# Solenoid_2.net
KiCad netlist of a schematic drawn in EAGLE
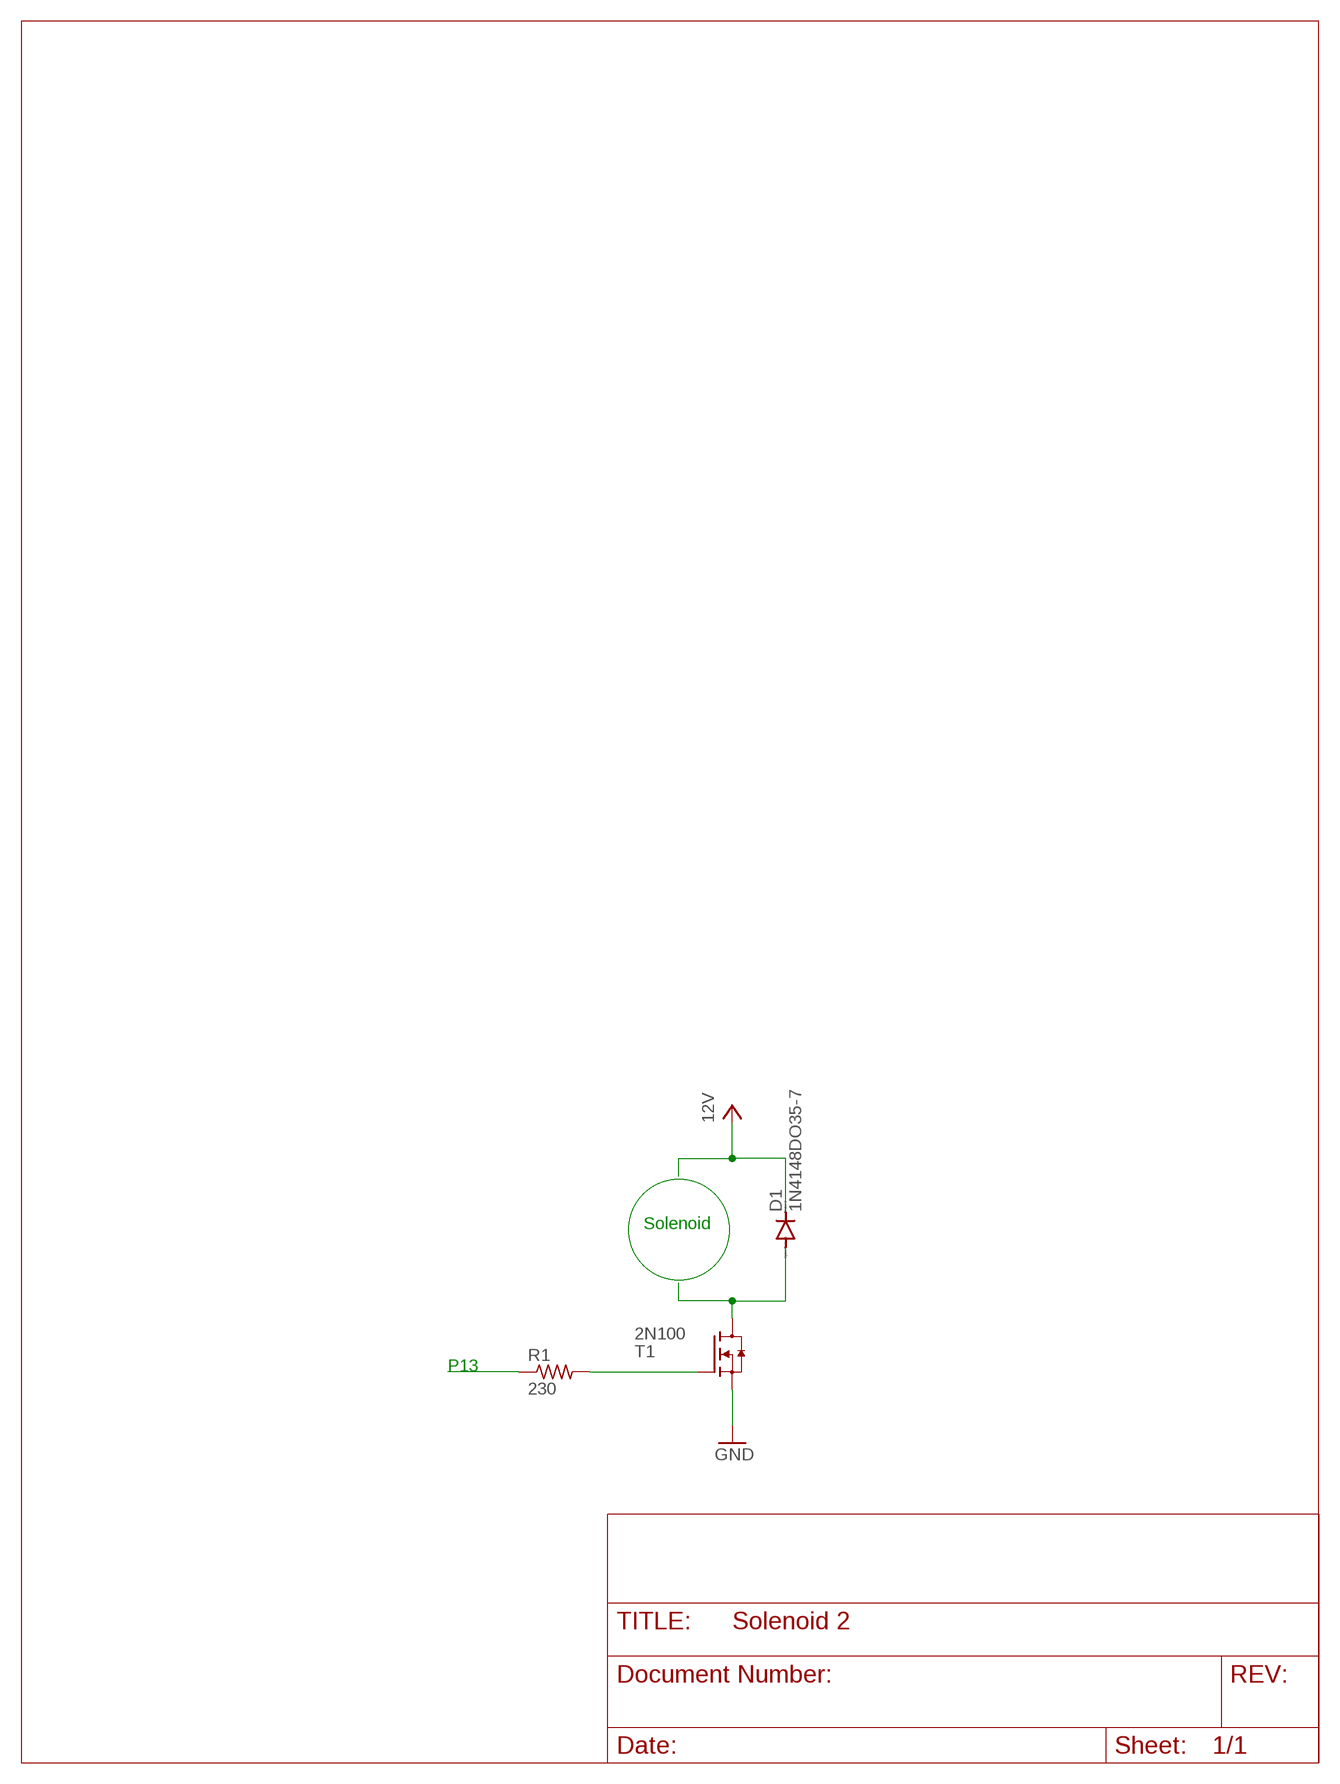
[diagram p0: schematic, sheet 1]

(export (version "E")
  (design (tool "Eeschema 10.0.6"))
  (components
    (comp (ref "D1")
      (value "1N4148DO35-7")
      (footprint "eagle-import:DO35-7")
      (libsource (lib "eagle-import") (part "1N4148DO35-7"))
    )
    (comp (ref "R1")
      (value "230")
      (footprint "eagle-import:0204_7")
      (libsource (lib "eagle-import") (part "R-US_0204/7"))
    )
    (comp (ref "T1")
      (value "2N100")
      (footprint "eagle-import:PG-TO263-7-3")
      (libsource (lib "eagle-import") (part "IPB180N06S4-H1"))
    )
  )
  (nets
    (net (code "1") (name "12V") (class "Default")
      (node (ref "D1") (pin "C") (pinfunction "C_C") (pintype "passive"))
    )
    (net (code "2") (name "GND") (class "Default")
      (node (ref "T1") (pin "2") (pinfunction "S_2") (pintype "passive"))
      (node (ref "T1") (pin "3") (pinfunction "S_3") (pintype "passive"))
      (node (ref "T1") (pin "5") (pinfunction "S_5") (pintype "passive"))
      (node (ref "T1") (pin "6") (pinfunction "S_6") (pintype "passive"))
      (node (ref "T1") (pin "7") (pinfunction "S_7") (pintype "passive"))
    )
    (net (code "3") (name "Net-(T1-D)") (class "Default")
      (node (ref "D1") (pin "A") (pinfunction "A_A") (pintype "passive"))
      (node (ref "T1") (pin "8") (pinfunction "D_8") (pintype "passive"))
    )
    (net (code "4") (name "Net-(T1-G)") (class "Default")
      (node (ref "R1") (pin "2") (pinfunction "2_2") (pintype "passive"))
      (node (ref "T1") (pin "1") (pinfunction "G_1") (pintype "passive"))
    )
    (net (code "5") (name "unconnected-(R1-Pad1)") (class "Default")
      (node (ref "R1") (pin "1") (pinfunction "1_1") (pintype "passive"))
    )
  )
)
